# SCH_Sol_rn_-m_i__2024-04-14.net
KiCad netlist of a schematic drawn in EasyEDA
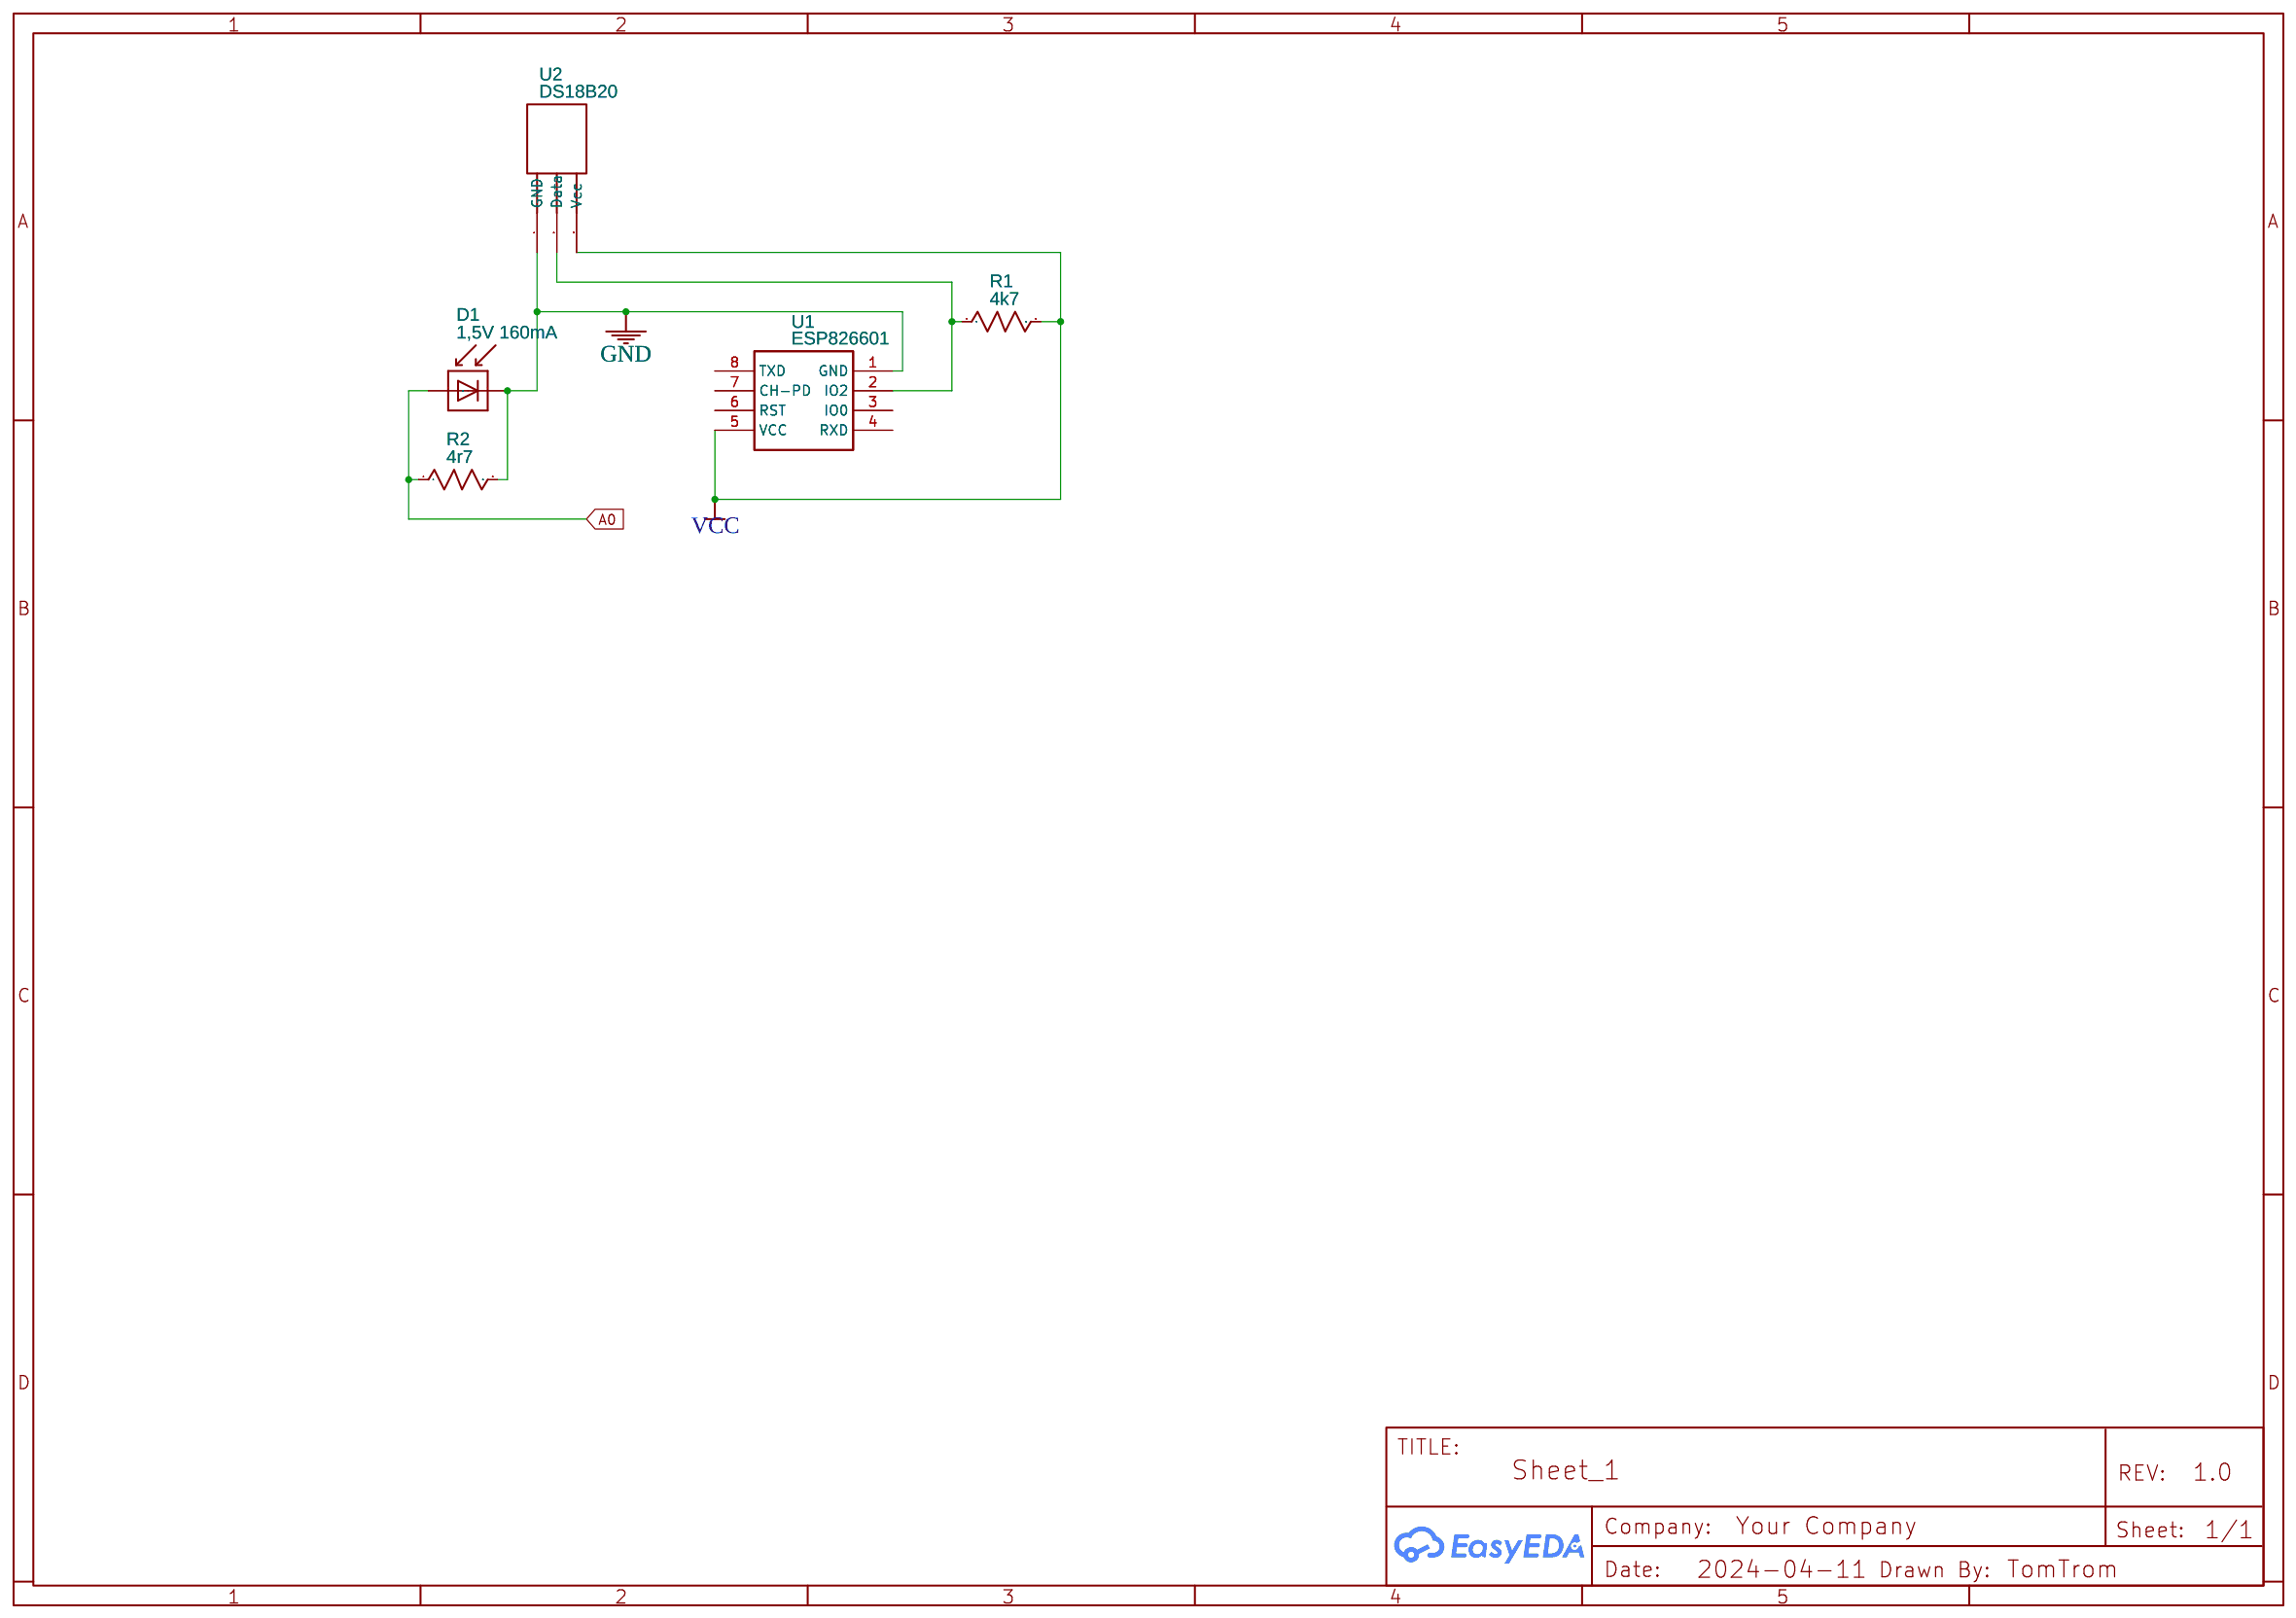
[diagram p0: schematic sheet]

(export (version "E")
  (design (tool "Eeschema 10.0.6"))
  (components
    (comp (ref "D1") (value "1,5V 160mA") (libsource (lib "") (part "‎KXOB25-14X1F‎")))
    (comp (ref "R1") (value "4k7") (libsource (lib "") (part "Resistor_US")))
    (comp (ref "R2") (value "4r7") (libsource (lib "") (part "Resistor_US")))
    (comp (ref "U1") (value "ESP826601") (libsource (lib "") (part "ESP826601")))
    (comp (ref "U2") (value "DS18B20") (libsource (lib "") (part "DS18B20")))
  )
  (nets
    (net (code "1") (name "A0") (class "Default")
      (node (ref "D1") (pin "+") (pinfunction "A_+") (pintype "unspecified"))
      (node (ref "R2") (pin "1") (pinfunction "1_1") (pintype "unspecified"))
    )
    (net (code "2") (name "GND") (class "Default")
      (node (ref "D1") (pin "-") (pinfunction "C_-") (pintype "unspecified"))
      (node (ref "R2") (pin "2") (pinfunction "2_2") (pintype "unspecified"))
      (node (ref "U1") (pin "1") (pinfunction "GND_1") (pintype "unspecified"))
      (node (ref "U2") (pin "1") (pinfunction "GND_1") (pintype "unspecified"))
    )
    (net (code "3") (name "Net-(U1-IO2)") (class "Default")
      (node (ref "R1") (pin "1") (pinfunction "1_1") (pintype "unspecified"))
      (node (ref "U1") (pin "2") (pinfunction "IO2_2") (pintype "unspecified"))
      (node (ref "U2") (pin "2") (pinfunction "Data_2") (pintype "unspecified"))
    )
    (net (code "4") (name "VCC") (class "Default")
      (node (ref "R1") (pin "2") (pinfunction "2_2") (pintype "unspecified"))
      (node (ref "U1") (pin "5") (pinfunction "VCC_5") (pintype "unspecified"))
      (node (ref "U2") (pin "3") (pinfunction "Vcc_3") (pintype "unspecified"))
    )
    (net (code "5") (name "unconnected-(U1-CH-PD-Pad7)") (class "Default")
      (node (ref "U1") (pin "7") (pinfunction "CH-PD_7") (pintype "unspecified"))
    )
    (net (code "6") (name "unconnected-(U1-IO0-Pad3)") (class "Default")
      (node (ref "U1") (pin "3") (pinfunction "IO0_3") (pintype "unspecified"))
    )
    (net (code "7") (name "unconnected-(U1-RST-Pad6)") (class "Default")
      (node (ref "U1") (pin "6") (pinfunction "RST_6") (pintype "unspecified"))
    )
    (net (code "8") (name "unconnected-(U1-RXD-Pad4)") (class "Default")
      (node (ref "U1") (pin "4") (pinfunction "RXD_4") (pintype "unspecified"))
    )
    (net (code "9") (name "unconnected-(U1-TXD-Pad8)") (class "Default")
      (node (ref "U1") (pin "8") (pinfunction "TXD_8") (pintype "unspecified"))
    )
  )
)
